# HV_DRV.net
KiCad netlist of a schematic drawn in Altium Designer
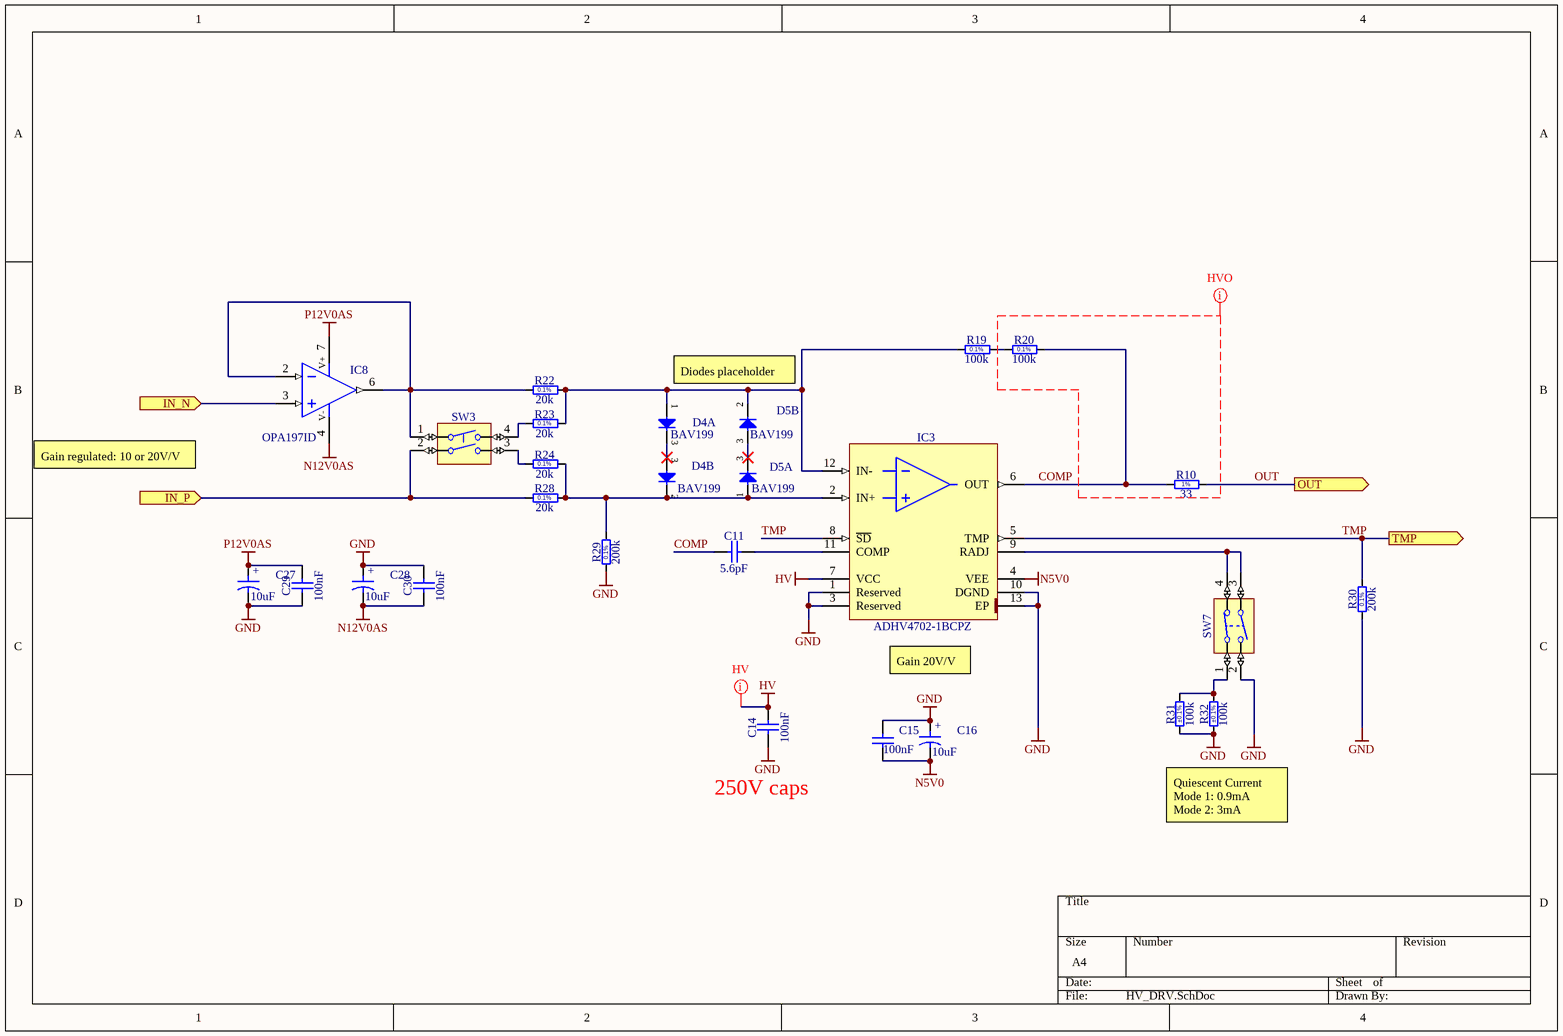
[diagram p0: HV_DRV.SchDoc]

(export (version "E")
  (design (tool "Eeschema 10.0.6"))
  (components
    (comp (ref "C11")
      (value "5.6pF")
      (footprint "CAPC3216X140N")
      (description "Non-polarised capacitor")
      (fields
        (field (name "PART NUMBER") "CC1206_5.6PF_50V_0.25PF_NP0")
        (field (name "VOLTAGE") "50V")
        (field (name "AUTHOR") "CERN DEM JLC")
      )
      (libsource (lib "Capacitors") (part "Capacitor - non polarized"))
    )
    (comp (ref "C14")
      (value "100nF")
      (footprint "CAPC4720X215N")
      (description "Non-polarised capacitor")
      (fields
        (field (name "PART NUMBER") "CC1808_100NF_630V_10%_X7R")
        (field (name "VOLTAGE") "630V")
        (field (name "AUTHOR") "CERN DEM MR")
      )
      (libsource (lib "Capacitors") (part "Capacitor - non polarized"))
    )
    (comp (ref "C15")
      (value "100nF")
      (footprint "CAPC1005X55N")
      (description "Non-polarised capacitor")
      (fields
        (field (name "PART NUMBER") "CC0402_100NF_16V_10%_X5R")
        (field (name "VOLTAGE") "16V")
        (field (name "AUTHOR") "CERN DEM JLC")
      )
      (libsource (lib "Capacitors") (part "Capacitor - non polarized"))
    )
    (comp (ref "C16")
      (value "10uF")
      (footprint "CAPMP3216X180N")
      (description "Polarised capacitor")
      (fields
        (field (name "PART NUMBER") "CTE3216-18_10UF_16V_20%_AVX_TCJ")
        (field (name "VOLTAGE") "16V")
        (field (name "AUTHOR") "CERN DEM JLC")
      )
      (libsource (lib "Capacitors") (part "Capacitor - polarized"))
    )
    (comp (ref "C27")
      (value "10uF")
      (footprint "CAPMP3216X180N")
      (description "Polarised capacitor")
      (fields
        (field (name "PART NUMBER") "CTE3216-18_10UF_16V_20%_AVX_TCJ")
        (field (name "VOLTAGE") "16V")
        (field (name "AUTHOR") "CERN DEM JLC")
      )
      (libsource (lib "Capacitors") (part "Capacitor - polarized"))
    )
    (comp (ref "C28")
      (value "10uF")
      (footprint "CAPMP3216X180N")
      (description "Polarised capacitor")
      (fields
        (field (name "PART NUMBER") "CTE3216-18_10UF_16V_20%_AVX_TCJ")
        (field (name "VOLTAGE") "16V")
        (field (name "AUTHOR") "CERN DEM JLC")
      )
      (libsource (lib "Capacitors") (part "Capacitor - polarized"))
    )
    (comp (ref "C29")
      (value "100nF")
      (footprint "CAPC1608X87N")
      (description "Non-polarised capacitor")
      (fields
        (field (name "PART NUMBER") "CC0603_100NF_50V_10%_X7R")
        (field (name "VOLTAGE") "50V")
        (field (name "AUTHOR") "CERN DEM JLC")
      )
      (libsource (lib "Capacitors") (part "Capacitor - non polarized"))
    )
    (comp (ref "C30")
      (value "100nF")
      (footprint "CAPC1608X87N")
      (description "Non-polarised capacitor")
      (fields
        (field (name "PART NUMBER") "CC0603_100NF_50V_10%_X7R")
        (field (name "VOLTAGE") "50V")
        (field (name "AUTHOR") "CERN DEM JLC")
      )
      (libsource (lib "Capacitors") (part "Capacitor - non polarized"))
    )
    (comp (ref "D4")
      (value "BAV199")
      (footprint "SOT95P240X110-3N")
      (description "Serial Diode")
      (fields
        (field (name "VOLTAGE") "75V")
        (field (name "POWER") "250mW")
        (field (name "AUTHOR") "CERN DEM JMW")
      )
      (libsource (lib "ICs And Semiconductors") (part "Diode x2 A1C3_A3C2"))
    )
    (comp (ref "D5")
      (value "BAV199")
      (footprint "SOT95P240X110-3N")
      (description "Serial Diode")
      (fields
        (field (name "VOLTAGE") "75V")
        (field (name "POWER") "250mW")
        (field (name "AUTHOR") "CERN DEM JMW")
      )
      (libsource (lib "ICs And Semiconductors") (part "Diode x2 A1C3_A3C2"))
    )
    (comp (ref "IC3")
      (value "ADHV4702-1BCPZ")
      (footprint "QFN170P700X700X80-13N-S290")
      (description "24V to 220V Precision Operational Amplifier")
      (fields (field (name "MANUFACTURER") "ANALOG DEVICES") (field (name "AUTHOR") "CERN DEM BC"))
      (libsource (lib "ICs And Semiconductors") (part "ADHV4702-1"))
    )
    (comp (ref "IC8")
      (value "OPA197ID")
      (footprint "SOIC127P600X175-8N")
      (description "Operational Amplifier")
      (fields (field (name "MANUFACTURER") "TEXAS INSTRUMENTS") (field (name "AUTHOR") "CERN DEM MR"))
      (libsource (lib "ICs And Semiconductors") (part "Operational Amplifier Type1"))
    )
    (comp (ref "R10")
      (value "33")
      (footprint "RESC2012X60N")
      (description "Resistor - 1%")
      (fields
        (field (name "PART NUMBER") "R0805_33R_1%_0.125W_100PPM")
        (field (name "POWER") "0.125W")
        (field (name "AUTHOR") "CERN DEM JLC")
      )
      (libsource (lib "Resistors") (part "Resistor - 1%"))
    )
    (comp (ref "R19")
      (value "100k")
      (footprint "RESC2012X60N")
      (description "Resistor - 0.1%")
      (fields
        (field (name "PART NUMBER") "R0805_100K_0.1%_0.1W_10PPM")
        (field (name "POWER") "0.1W")
        (field (name "AUTHOR") "CERN DEM JLC")
      )
      (libsource (lib "Resistors") (part "Resistor - 0.1%"))
    )
    (comp (ref "R20")
      (value "100k")
      (footprint "RESC2012X60N")
      (description "Resistor - 0.1%")
      (fields
        (field (name "PART NUMBER") "R0805_100K_0.1%_0.1W_10PPM")
        (field (name "POWER") "0.1W")
        (field (name "AUTHOR") "CERN DEM JLC")
      )
      (libsource (lib "Resistors") (part "Resistor - 0.1%"))
    )
    (comp (ref "R22")
      (value "20k")
      (footprint "RESC1608X55N")
      (description "Resistor - 0.1%")
      (fields
        (field (name "PART NUMBER") "R0603_20K_0.1%_0.063W_10PPM")
        (field (name "POWER") "0.063W")
        (field (name "AUTHOR") "CERN DEM JLC")
      )
      (libsource (lib "Resistors") (part "Resistor - 0.1%"))
    )
    (comp (ref "R23")
      (value "20k")
      (footprint "RESC1608X55N")
      (description "Resistor - 0.1%")
      (fields
        (field (name "PART NUMBER") "R0603_20K_0.1%_0.063W_10PPM")
        (field (name "POWER") "0.063W")
        (field (name "AUTHOR") "CERN DEM JLC")
      )
      (libsource (lib "Resistors") (part "Resistor - 0.1%"))
    )
    (comp (ref "R24")
      (value "20k")
      (footprint "RESC1608X55N")
      (description "Resistor - 0.1%")
      (fields
        (field (name "PART NUMBER") "R0603_20K_0.1%_0.063W_10PPM")
        (field (name "POWER") "0.063W")
        (field (name "AUTHOR") "CERN DEM JLC")
      )
      (libsource (lib "Resistors") (part "Resistor - 0.1%"))
    )
    (comp (ref "R28")
      (value "20k")
      (footprint "RESC1608X55N")
      (description "Resistor - 0.1%")
      (fields
        (field (name "PART NUMBER") "R0603_20K_0.1%_0.063W_10PPM")
        (field (name "POWER") "0.063W")
        (field (name "AUTHOR") "CERN DEM JLC")
      )
      (libsource (lib "Resistors") (part "Resistor - 0.1%"))
    )
    (comp (ref "R29")
      (value "200k")
      (footprint "RESC1608X55N")
      (description "Resistor - 0.1%")
      (fields
        (field (name "PART NUMBER") "R0603_200K_0.1%_0.063W_10PPM")
        (field (name "POWER") "0.063W")
        (field (name "AUTHOR") "CERN DEM MR")
      )
      (libsource (lib "Resistors") (part "Resistor - 0.1%"))
    )
    (comp (ref "R30")
      (value "200k")
      (footprint "RESC1608X55N")
      (description "Resistor - 0.1%")
      (fields
        (field (name "PART NUMBER") "R0603_200K_0.1%_0.063W_10PPM")
        (field (name "POWER") "0.063W")
        (field (name "AUTHOR") "CERN DEM MR")
      )
      (libsource (lib "Resistors") (part "Resistor - 0.1%"))
    )
    (comp (ref "R31")
      (value "100k")
      (footprint "RESC1005X35N")
      (description "Resistor - 0.1%")
      (fields
        (field (name "TOLERANCE") "±0.1%")
        (field (name "PART NUMBER") "R0402_100K_0.1%_0.063W_25PPM")
        (field (name "POWER") "0.063W")
        (field (name "AUTHOR") "CERN DEM JMW")
      )
      (libsource (lib "") (part "Resistor - 0.1%_1"))
    )
    (comp (ref "R32")
      (value "100k")
      (footprint "RESC1005X35N")
      (description "Resistor - 0.1%")
      (fields
        (field (name "TOLERANCE") "±0.1%")
        (field (name "PART NUMBER") "R0402_100K_0.1%_0.063W_25PPM")
        (field (name "POWER") "0.063W")
        (field (name "AUTHOR") "CERN DEM JMW")
      )
      (libsource (lib "") (part "Resistor - 0.1%_1"))
    )
    (comp (ref "SW3")
      (value "Switch")
      (footprint "SW_ERG_SDD-1-023")
      (description "DPST DIP Switch")
      (fields
        (field (name "PART NUMBER") "SW_ERG_SDD-1-023")
        (field (name "MANUFACTURER") "ITW ERG")
        (field (name "AUTHOR") "CERN DEM JLC")
      )
      (libsource (lib "Eletro-mechanical") (part "SW 1x DPST DIP Switch"))
    )
    (comp (ref "SW7")
      (value "Switch")
      (footprint "SW_CTS_204-121ST")
      (description "2x SPST DIP Switch 1NO + 1NF")
      (fields
        (field (name "PART NUMBER") "SW_CTS_204-121ST")
        (field (name "MANUFACTURER") "CTS")
        (field (name "AUTHOR") "CERN DEM JLC")
      )
      (libsource (lib "Eletro-mechanical") (part "SW_CTS_204-121ST"))
    )
  )
  (nets
    (net (code "2") (name "/COMP") (class "Default")
      (node (ref "C11") (pin "1") (pinfunction "1_1") (pintype "passive"))
      (node (ref "IC3") (pin "6") (pinfunction "OUT_6") (pintype "output"))
      (node (ref "R10") (pin "1") (pinfunction "1_1") (pintype "passive"))
      (node (ref "R20") (pin "2") (pinfunction "2_2") (pintype "passive"))
    )
    (net (code "3") (name "/IN_N") (class "Default")
      (node (ref "IC8") (pin "3") (pinfunction "IN+_3") (pintype "input"))
    )
    (net (code "4") (name "/IN_P") (class "Default")
      (node (ref "R28") (pin "1") (pinfunction "1_1") (pintype "passive"))
      (node (ref "SW3") (pin "2") (pinfunction "2_2") (pintype "bidirectional"))
    )
    (net (code "5") (name "/OUT") (class "Default")
      (node (ref "R10") (pin "2") (pinfunction "2_2") (pintype "passive"))
    )
    (net (code "6") (name "/TMP") (class "Default")
      (node (ref "IC3") (pin "5") (pinfunction "TMP_5") (pintype "output"))
      (node (ref "IC3") (pin "8") (pinfunction "~{SD}_8") (pintype "input"))
      (node (ref "R30") (pin "2") (pinfunction "2_2") (pintype "passive"))
    )
    (net (code "7") (name "GND") (class "Default")
      (node (ref "C14") (pin "1") (pinfunction "1_1") (pintype "passive"))
      (node (ref "C15") (pin "2") (pinfunction "2_2") (pintype "passive"))
      (node (ref "C16") (pin "1") (pinfunction "1_1") (pintype "passive"))
      (node (ref "C27") (pin "2") (pinfunction "2_2") (pintype "passive"))
      (node (ref "C28") (pin "1") (pinfunction "1_1") (pintype "passive"))
      (node (ref "C29") (pin "1") (pinfunction "1_1") (pintype "passive"))
      (node (ref "C30") (pin "2") (pinfunction "2_2") (pintype "passive"))
      (node (ref "IC3") (pin "1") (pinfunction "Reserved_1") (pintype "passive"))
      (node (ref "IC3") (pin "10") (pinfunction "DGND_10") (pintype "power_in"))
      (node (ref "IC3") (pin "13") (pinfunction "EP_13") (pintype "passive"))
      (node (ref "IC3") (pin "3") (pinfunction "Reserved_3") (pintype "passive"))
      (node (ref "R29") (pin "1") (pinfunction "1_1") (pintype "passive"))
      (node (ref "R30") (pin "1") (pinfunction "1_1") (pintype "passive"))
      (node (ref "R31") (pin "1") (pinfunction "1_1") (pintype "passive"))
      (node (ref "R32") (pin "1") (pinfunction "1_1") (pintype "passive"))
      (node (ref "SW7") (pin "2") (pinfunction "2_2") (pintype "bidirectional"))
    )
    (net (code "8") (name "HV") (class "Default")
      (node (ref "C14") (pin "2") (pinfunction "2_2") (pintype "passive"))
      (node (ref "IC3") (pin "7") (pinfunction "VCC_7") (pintype "power_in"))
    )
    (net (code "9") (name "N5V0") (class "Default")
      (node (ref "C15") (pin "1") (pinfunction "1_1") (pintype "passive"))
      (node (ref "C16") (pin "2") (pinfunction "2_2") (pintype "passive"))
      (node (ref "IC3") (pin "4") (pinfunction "VEE_4") (pintype "power_in"))
    )
    (net (code "10") (name "N12V0AS") (class "Default")
      (node (ref "C28") (pin "2") (pinfunction "2_2") (pintype "passive"))
      (node (ref "C30") (pin "1") (pinfunction "1_1") (pintype "passive"))
      (node (ref "IC8") (pin "4") (pinfunction "V-_4") (pintype "power_in"))
    )
    (net (code "11") (name "Net-(D4A-A)") (class "Default")
      (node (ref "D4") (pin "1") (pinfunction "A_1") (pintype "passive"))
      (node (ref "D5") (pin "2") (pinfunction "C_2") (pintype "passive"))
      (node (ref "IC3") (pin "12") (pinfunction "IN-_12") (pintype "input"))
      (node (ref "R19") (pin "1") (pinfunction "1_1") (pintype "passive"))
      (node (ref "R22") (pin "2") (pinfunction "2_2") (pintype "passive"))
      (node (ref "R23") (pin "2") (pinfunction "2_2") (pintype "passive"))
    )
    (net (code "12") (name "Net-(D4B-C)") (class "Default")
      (node (ref "D4") (pin "2") (pinfunction "C_2") (pintype "passive"))
      (node (ref "D5") (pin "1") (pinfunction "A_1") (pintype "passive"))
      (node (ref "IC3") (pin "2") (pinfunction "IN+_2") (pintype "input"))
      (node (ref "R24") (pin "2") (pinfunction "2_2") (pintype "passive"))
      (node (ref "R28") (pin "2") (pinfunction "2_2") (pintype "passive"))
      (node (ref "R29") (pin "2") (pinfunction "2_2") (pintype "passive"))
    )
    (net (code "13") (name "Net-(IC3-COMP)") (class "Default")
      (node (ref "C11") (pin "2") (pinfunction "2_2") (pintype "passive"))
      (node (ref "IC3") (pin "11") (pinfunction "COMP_11") (pintype "passive"))
    )
    (net (code "14") (name "Net-(IC3-RADJ)") (class "Default")
      (node (ref "IC3") (pin "9") (pinfunction "RADJ_9") (pintype "passive"))
      (node (ref "SW7") (pin "3") (pinfunction "3_3") (pintype "bidirectional"))
      (node (ref "SW7") (pin "4") (pinfunction "4_4") (pintype "bidirectional"))
    )
    (net (code "15") (name "Net-(IC8-IN-)") (class "Default")
      (node (ref "IC8") (pin "2") (pinfunction "IN-_2") (pintype "input"))
      (node (ref "IC8") (pin "6") (pinfunction "OUT_6") (pintype "output"))
      (node (ref "R22") (pin "1") (pinfunction "1_1") (pintype "passive"))
      (node (ref "SW3") (pin "1") (pinfunction "1_1") (pintype "bidirectional"))
    )
    (net (code "16") (name "Net-(R19-Pad2)") (class "Default")
      (node (ref "R19") (pin "2") (pinfunction "2_2") (pintype "passive"))
      (node (ref "R20") (pin "1") (pinfunction "1_1") (pintype "passive"))
    )
    (net (code "17") (name "Net-(R23-Pad1)") (class "Default")
      (node (ref "R23") (pin "1") (pinfunction "1_1") (pintype "passive"))
      (node (ref "SW3") (pin "4") (pinfunction "4_4") (pintype "bidirectional"))
    )
    (net (code "18") (name "Net-(R24-Pad1)") (class "Default")
      (node (ref "R24") (pin "1") (pinfunction "1_1") (pintype "passive"))
      (node (ref "SW3") (pin "3") (pinfunction "3_3") (pintype "bidirectional"))
    )
    (net (code "19") (name "Net-(R31-Pad2)") (class "Default")
      (node (ref "R31") (pin "2") (pinfunction "2_2") (pintype "passive"))
      (node (ref "R32") (pin "2") (pinfunction "2_2") (pintype "passive"))
      (node (ref "SW7") (pin "1") (pinfunction "1_1") (pintype "bidirectional"))
    )
    (net (code "20") (name "P12V0AS") (class "Default")
      (node (ref "C27") (pin "1") (pinfunction "1_1") (pintype "passive"))
      (node (ref "C29") (pin "2") (pinfunction "2_2") (pintype "passive"))
      (node (ref "IC8") (pin "7") (pinfunction "V+_7") (pintype "power_in"))
    )
    (net (code "21") (name "unconnected-(D4A-COMAC-Pad3)") (class "Default")
      (node (ref "D4") (pin "3") (pinfunction "COMAC_3") (pintype "passive+no_connect"))
    )
    (net (code "22") (name "unconnected-(D5A-COMAC-Pad3)") (class "Default")
      (node (ref "D5") (pin "3") (pinfunction "COMAC_3") (pintype "passive+no_connect"))
    )
  )
)
